# WELLD0_3Schematic.net
KiCad netlist of a schematic drawn in EAGLE
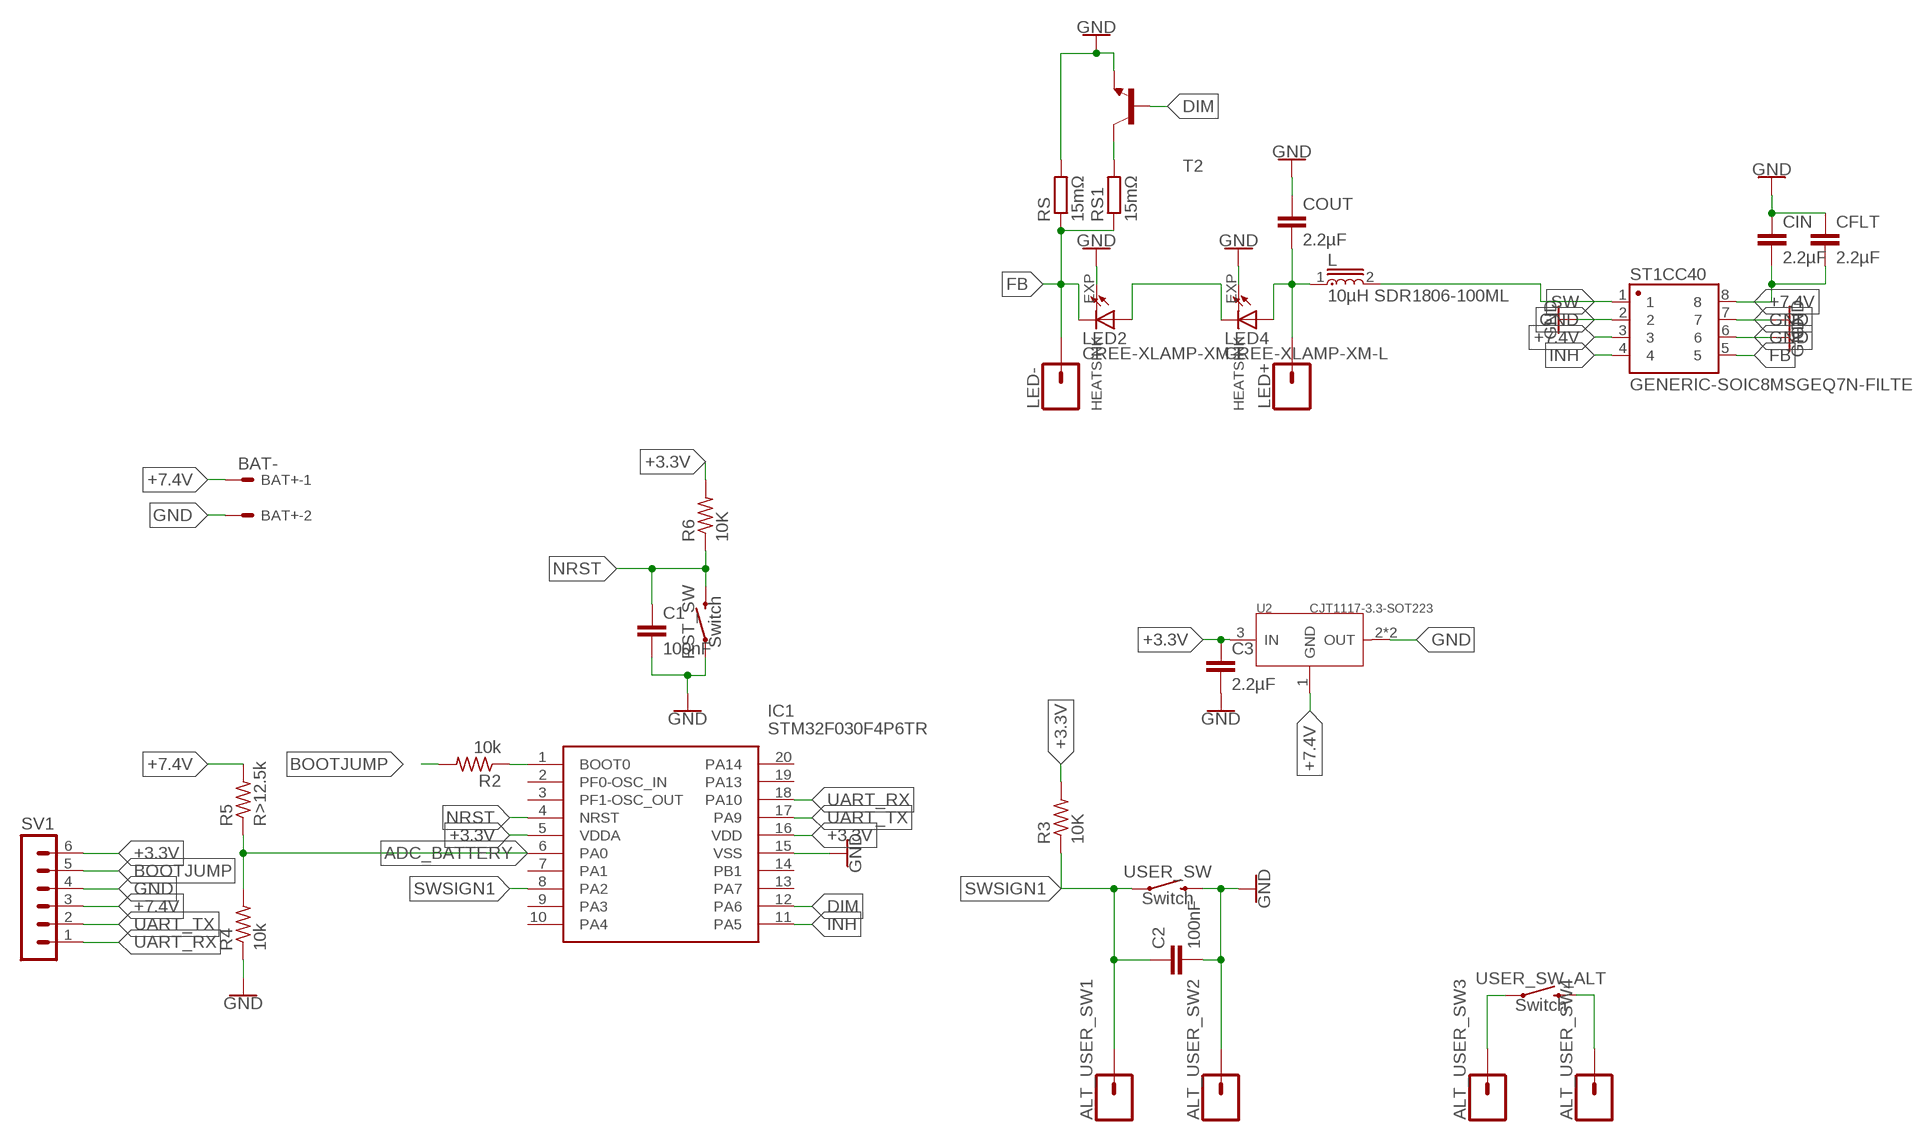
[diagram p0: schematic, sheet 1]

(export (version "E")
  (design (tool "Eeschema 10.0.6"))
  (components
    (comp (ref "ALT_USER_SW1")
      (value "CONN_01")
      (footprint "eagle-import:1X01")
      (libsource (lib "eagle-import") (part "CONN_01"))
    )
    (comp (ref "ALT_USER_SW2")
      (value "CONN_01")
      (footprint "eagle-import:1X01")
      (libsource (lib "eagle-import") (part "CONN_01"))
    )
    (comp (ref "ALT_USER_SW3")
      (value "CONN_01")
      (footprint "eagle-import:1X01")
      (libsource (lib "eagle-import") (part "CONN_01"))
    )
    (comp (ref "ALT_USER_SW4")
      (value "CONN_01")
      (footprint "eagle-import:1X01")
      (libsource (lib "eagle-import") (part "CONN_01"))
    )
    (comp (ref "BAT+")
      (value "BAT-")
      (footprint "eagle-import:6410-02")
      (fields (field (name "MF") "MOLEX"))
      (libsource (lib "eagle-import") (part "22-?-0227-2021"))
    )
    (comp (ref "C1")
      (value "100nF")
      (footprint "eagle-import:C0603")
      (libsource (lib "eagle-import") (part "C-EUC0603"))
    )
    (comp (ref "C2")
      (value "100nF")
      (footprint "eagle-import:C0603")
      (libsource (lib "eagle-import") (part "C-EUC0603"))
    )
    (comp (ref "C3")
      (value "2.2µF")
      (footprint "eagle-import:C0603")
      (libsource (lib "eagle-import") (part "C-EUC0603"))
    )
    (comp (ref "CFLT")
      (value "2.2µF")
      (footprint "eagle-import:C0603")
      (libsource (lib "eagle-import") (part "C-EUC0603"))
    )
    (comp (ref "CIN")
      (value "2.2µF")
      (footprint "eagle-import:C0603")
      (libsource (lib "eagle-import") (part "C-EUC0603"))
    )
    (comp (ref "COUT")
      (value "2.2µF")
      (footprint "eagle-import:C0603")
      (libsource (lib "eagle-import") (part "C-EUC0603"))
    )
    (comp (ref "IC1")
      (value "STM32F030F4P6TR")
      (footprint "eagle-import:SOP65P640X120-20N")
      (fields (field (name "RS_PART_NUMBER") "1688744"))
      (libsource (lib "eagle-import") (part "STM32F030F4P6TR"))
    )
    (comp (ref "L")
      (value "10µH SDR1806-100ML")
      (footprint "eagle-import:INDP1830X1400X690L250X260N")
      (fields
        (field (name "DIGI-KEY_PART_NUMBER") "SDR1806-470MLCT-ND")
        (field (name "MF") "Bourns")
        (field (name "MP") "SDR1806-470ML")
      )
      (libsource (lib "eagle-import") (part "SDR1806-470ML"))
    )
    (comp (ref "LED+")
      (value "CONN_01")
      (footprint "eagle-import:1X01")
      (libsource (lib "eagle-import") (part "CONN_01"))
    )
    (comp (ref "LED-")
      (value "CONN_01")
      (footprint "eagle-import:1X01")
      (libsource (lib "eagle-import") (part "CONN_01"))
    )
    (comp (ref "LED2")
      (value "CREE-XLAMP-XM-L")
      (footprint "eagle-import:CREE-XLAMP-XM-L")
      (libsource (lib "eagle-import") (part "CREE-XLAMP-XM-L"))
    )
    (comp (ref "LED4")
      (value "CREE-XLAMP-XM-L")
      (footprint "eagle-import:CREE-XLAMP-XM-L")
      (libsource (lib "eagle-import") (part "CREE-XLAMP-XM-L"))
    )
    (comp (ref "R2")
      (value "10k")
      (footprint "eagle-import:R0603")
      (libsource (lib "eagle-import") (part "R-US_R0603"))
    )
    (comp (ref "R3")
      (value "10K")
      (footprint "eagle-import:R0603")
      (libsource (lib "eagle-import") (part "R-US_R0603"))
    )
    (comp (ref "R4")
      (value "10k")
      (footprint "eagle-import:R0603")
      (libsource (lib "eagle-import") (part "R-US_R0603"))
    )
    (comp (ref "R5")
      (value "R>12.5k")
      (footprint "eagle-import:R0603")
      (libsource (lib "eagle-import") (part "R-US_R0603"))
    )
    (comp (ref "R6")
      (value "10K")
      (footprint "eagle-import:R0603")
      (libsource (lib "eagle-import") (part "R-US_R0603"))
    )
    (comp (ref "RS")
      (value "15mΩ")
      (footprint "eagle-import:M1206")
      (libsource (lib "eagle-import") (part "R-EU_M1206"))
    )
    (comp (ref "RS1")
      (value "15mΩ")
      (footprint "eagle-import:M1206")
      (libsource (lib "eagle-import") (part "R-EU_M1206"))
    )
    (comp (ref "RST_SW")
      (value "Switch")
      (footprint "eagle-import:TACTILE_SWITCH_SMD_6.2MM_TALL")
      (libsource (lib "eagle-import") (part "MOMENTARY-SWITCH-SPST-SMD-6.2MM-TALL"))
    )
    (comp (ref "ST1CC40")
      (value "GENERIC-SOIC8MSGEQ7N-FILTER")
      (footprint "eagle-import:SO08")
      (libsource (lib "eagle-import") (part "GENERIC-SOIC8MSGEQ7N-FILTER"))
    )
    (comp (ref "SV1")
      (value "MA06-1")
      (footprint "eagle-import:MA06-1")
      (libsource (lib "eagle-import") (part "MA06-1"))
    )
    (comp (ref "T2")
      (value "-NPN-SOT23-BEC")
      (footprint "eagle-import:SOT23-BEC")
      (libsource (lib "eagle-import") (part "-NPN-SOT23-BEC"))
    )
    (comp (ref "U2")
      (value "CJT1117-3.3-SOT223")
      (footprint "eagle-import:SOT-223")
      (fields (field (name "MPN") "CJT1117-3.3"))
      (libsource (lib "eagle-import") (part "PMIC-CJT1117-3.3(SOT223)"))
    )
    (comp (ref "USER_SW")
      (value "Switch")
      (footprint "eagle-import:TACTILE_SWITCH_SMD_6.2MM_TALL")
      (libsource (lib "eagle-import") (part "MOMENTARY-SWITCH-SPST-SMD-6.2MM-TALL"))
    )
    (comp (ref "USER_SW_ALT")
      (value "Switch")
      (footprint "eagle-import:TACTILE_SWITCH_SMD_6.2MM_TALL")
      (libsource (lib "eagle-import") (part "MOMENTARY-SWITCH-SPST-SMD-6.2MM-TALL"))
    )
  )
  (nets
    (net (code "1") (name "+3.3V") (class "Default")
      (node (ref "C3") (pin "1") (pinfunction "1_1") (pintype "passive"))
      (node (ref "IC1") (pin "16") (pinfunction "VDD_16") (pintype "power_in"))
      (node (ref "IC1") (pin "5") (pinfunction "VDDA_5") (pintype "power_in"))
      (node (ref "R3") (pin "2") (pinfunction "2_2") (pintype "passive"))
      (node (ref "R6") (pin "2") (pinfunction "2_2") (pintype "passive"))
      (node (ref "SV1") (pin "6") (pinfunction "6_6") (pintype "passive"))
      (node (ref "U2") (pin "3") (pinfunction "IN_3") (pintype "bidirectional"))
    )
    (net (code "2") (name "+7.4V") (class "Default")
      (node (ref "BAT+") (pin "1") (pinfunction "S_1") (pintype "passive"))
      (node (ref "CFLT") (pin "2") (pinfunction "2_2") (pintype "passive"))
      (node (ref "CIN") (pin "2") (pinfunction "2_2") (pintype "passive"))
      (node (ref "R5") (pin "2") (pinfunction "2_2") (pintype "passive"))
      (node (ref "ST1CC40") (pin "3") (pinfunction "3_3") (pintype "bidirectional"))
      (node (ref "ST1CC40") (pin "8") (pinfunction "8_8") (pintype "bidirectional"))
      (node (ref "SV1") (pin "3") (pinfunction "3_3") (pintype "passive"))
      (node (ref "U2") (pin "1") (pinfunction "GND_1") (pintype "bidirectional"))
    )
    (net (code "3") (name "ADC_BATTERY") (class "Default")
      (node (ref "IC1") (pin "6") (pinfunction "PA0_6") (pintype "bidirectional"))
      (node (ref "R4") (pin "2") (pinfunction "2_2") (pintype "passive"))
      (node (ref "R5") (pin "1") (pinfunction "1_1") (pintype "passive"))
    )
    (net (code "4") (name "BOOTJUMP") (class "Default")
      (node (ref "R2") (pin "2") (pinfunction "2_2") (pintype "passive"))
      (node (ref "SV1") (pin "5") (pinfunction "5_5") (pintype "passive"))
    )
    (net (code "5") (name "DIM") (class "Default")
      (node (ref "IC1") (pin "12") (pinfunction "PA6_12") (pintype "bidirectional"))
      (node (ref "T2") (pin "B") (pinfunction "B_B") (pintype "passive"))
    )
    (net (code "6") (name "FB") (class "Default")
      (node (ref "LED-") (pin "1") (pinfunction "1_1") (pintype "passive"))
      (node (ref "LED2") (pin "C") (pinfunction "C_C") (pintype "passive"))
      (node (ref "LED2") (pin "C@1") (pinfunction "C_C@1") (pintype "passive"))
      (node (ref "RS") (pin "1") (pinfunction "1_1") (pintype "passive"))
      (node (ref "RS1") (pin "1") (pinfunction "1_1") (pintype "passive"))
      (node (ref "ST1CC40") (pin "5") (pinfunction "5_5") (pintype "bidirectional"))
    )
    (net (code "7") (name "GND") (class "Default")
      (node (ref "ALT_USER_SW2") (pin "1") (pinfunction "1_1") (pintype "passive"))
      (node (ref "BAT+") (pin "2") (pinfunction "S_2") (pintype "passive"))
      (node (ref "C1") (pin "2") (pinfunction "2_2") (pintype "passive"))
      (node (ref "C2") (pin "2") (pinfunction "2_2") (pintype "passive"))
      (node (ref "C3") (pin "2") (pinfunction "2_2") (pintype "passive"))
      (node (ref "CFLT") (pin "1") (pinfunction "1_1") (pintype "passive"))
      (node (ref "CIN") (pin "1") (pinfunction "1_1") (pintype "passive"))
      (node (ref "COUT") (pin "1") (pinfunction "1_1") (pintype "passive"))
      (node (ref "IC1") (pin "15") (pinfunction "VSS_15") (pintype "power_in"))
      (node (ref "LED2") (pin "EXP") (pinfunction "HEATSINK_EXP") (pintype "bidirectional"))
      (node (ref "LED4") (pin "EXP") (pinfunction "HEATSINK_EXP") (pintype "bidirectional"))
      (node (ref "R4") (pin "1") (pinfunction "1_1") (pintype "passive"))
      (node (ref "RS") (pin "2") (pinfunction "2_2") (pintype "passive"))
      (node (ref "RST_SW") (pin "A2") (pinfunction "1_A2") (pintype "passive"))
      (node (ref "ST1CC40") (pin "2") (pinfunction "2_2") (pintype "bidirectional"))
      (node (ref "ST1CC40") (pin "6") (pinfunction "6_6") (pintype "bidirectional"))
      (node (ref "ST1CC40") (pin "7") (pinfunction "7_7") (pintype "bidirectional"))
      (node (ref "SV1") (pin "4") (pinfunction "4_4") (pintype "passive"))
      (node (ref "T2") (pin "E") (pinfunction "E_E") (pintype "passive"))
      (node (ref "U2") (pin "2") (pinfunction "OUT_2") (pintype "bidirectional"))
      (node (ref "U2") (pin "TER") (pinfunction "OUT_TER") (pintype "bidirectional"))
      (node (ref "USER_SW") (pin "B2") (pinfunction "2_B2") (pintype "passive"))
    )
    (net (code "8") (name "INH") (class "Default")
      (node (ref "IC1") (pin "11") (pinfunction "PA5_11") (pintype "bidirectional"))
      (node (ref "ST1CC40") (pin "4") (pinfunction "4_4") (pintype "bidirectional"))
    )
    (net (code "9") (name "NRST") (class "Default")
      (node (ref "C1") (pin "1") (pinfunction "1_1") (pintype "passive"))
      (node (ref "IC1") (pin "4") (pinfunction "NRST_4") (pintype "input"))
      (node (ref "R6") (pin "1") (pinfunction "1_1") (pintype "passive"))
      (node (ref "RST_SW") (pin "B2") (pinfunction "2_B2") (pintype "passive"))
    )
    (net (code "10") (name "Net-(COUT-Pad2)") (class "Default")
      (node (ref "COUT") (pin "2") (pinfunction "2_2") (pintype "passive"))
      (node (ref "L") (pin "1") (pinfunction "1_1") (pintype "passive"))
      (node (ref "LED+") (pin "1") (pinfunction "1_1") (pintype "passive"))
      (node (ref "LED4") (pin "A") (pinfunction "A_A") (pintype "passive"))
      (node (ref "LED4") (pin "A@1") (pinfunction "A_A@1") (pintype "passive"))
    )
    (net (code "11") (name "Net-(IC1-BOOT0)") (class "Default")
      (node (ref "IC1") (pin "1") (pinfunction "BOOT0_1") (pintype "bidirectional"))
      (node (ref "R2") (pin "1") (pinfunction "1_1") (pintype "passive"))
    )
    (net (code "12") (name "Net-(LED2-A-PadA@1)") (class "Default")
      (node (ref "LED2") (pin "A") (pinfunction "A_A") (pintype "passive"))
      (node (ref "LED2") (pin "A@1") (pinfunction "A_A@1") (pintype "passive"))
      (node (ref "LED4") (pin "C") (pinfunction "C_C") (pintype "passive"))
      (node (ref "LED4") (pin "C@1") (pinfunction "C_C@1") (pintype "passive"))
    )
    (net (code "13") (name "Net-(RS1-Pad2)") (class "Default")
      (node (ref "RS1") (pin "2") (pinfunction "2_2") (pintype "passive"))
      (node (ref "T2") (pin "C") (pinfunction "C_C") (pintype "passive"))
    )
    (net (code "14") (name "Net-(USER_SW_ALT-1)") (class "Default")
      (node (ref "ALT_USER_SW3") (pin "1") (pinfunction "1_1") (pintype "passive"))
      (node (ref "USER_SW_ALT") (pin "A2") (pinfunction "1_A2") (pintype "passive"))
    )
    (net (code "15") (name "Net-(USER_SW_ALT-2)") (class "Default")
      (node (ref "ALT_USER_SW4") (pin "1") (pinfunction "1_1") (pintype "passive"))
      (node (ref "USER_SW_ALT") (pin "B2") (pinfunction "2_B2") (pintype "passive"))
    )
    (net (code "16") (name "SW") (class "Default")
      (node (ref "L") (pin "2") (pinfunction "2_2") (pintype "passive"))
      (node (ref "ST1CC40") (pin "1") (pinfunction "1_1") (pintype "bidirectional"))
    )
    (net (code "17") (name "SWSIGN1") (class "Default")
      (node (ref "ALT_USER_SW1") (pin "1") (pinfunction "1_1") (pintype "passive"))
      (node (ref "C2") (pin "1") (pinfunction "1_1") (pintype "passive"))
      (node (ref "IC1") (pin "8") (pinfunction "PA2_8") (pintype "bidirectional"))
      (node (ref "R3") (pin "1") (pinfunction "1_1") (pintype "passive"))
      (node (ref "USER_SW") (pin "A2") (pinfunction "1_A2") (pintype "passive"))
    )
    (net (code "18") (name "UART_RX") (class "Default")
      (node (ref "IC1") (pin "18") (pinfunction "PA10_18") (pintype "bidirectional"))
      (node (ref "SV1") (pin "1") (pinfunction "1_1") (pintype "passive"))
    )
    (net (code "19") (name "UART_TX") (class "Default")
      (node (ref "IC1") (pin "17") (pinfunction "PA9_17") (pintype "bidirectional"))
      (node (ref "SV1") (pin "2") (pinfunction "2_2") (pintype "passive"))
    )
    (net (code "20") (name "unconnected-(IC1-PA1-Pad7)") (class "Default")
      (node (ref "IC1") (pin "7") (pinfunction "PA1_7") (pintype "bidirectional"))
    )
    (net (code "21") (name "unconnected-(IC1-PA3-Pad9)") (class "Default")
      (node (ref "IC1") (pin "9") (pinfunction "PA3_9") (pintype "bidirectional"))
    )
    (net (code "22") (name "unconnected-(IC1-PA4-Pad10)") (class "Default")
      (node (ref "IC1") (pin "10") (pinfunction "PA4_10") (pintype "bidirectional"))
    )
    (net (code "23") (name "unconnected-(IC1-PA7-Pad13)") (class "Default")
      (node (ref "IC1") (pin "13") (pinfunction "PA7_13") (pintype "bidirectional"))
    )
    (net (code "24") (name "unconnected-(IC1-PA13-Pad19)") (class "Default")
      (node (ref "IC1") (pin "19") (pinfunction "PA13_19") (pintype "bidirectional"))
    )
    (net (code "25") (name "unconnected-(IC1-PA14-Pad20)") (class "Default")
      (node (ref "IC1") (pin "20") (pinfunction "PA14_20") (pintype "bidirectional"))
    )
    (net (code "26") (name "unconnected-(IC1-PB1-Pad14)") (class "Default")
      (node (ref "IC1") (pin "14") (pinfunction "PB1_14") (pintype "bidirectional"))
    )
    (net (code "27") (name "unconnected-(IC1-PF0-OSC_IN-Pad2)") (class "Default")
      (node (ref "IC1") (pin "2") (pinfunction "PF0-OSC_IN_2") (pintype "input"))
    )
    (net (code "28") (name "unconnected-(IC1-PF1-OSC_OUT-Pad3)") (class "Default")
      (node (ref "IC1") (pin "3") (pinfunction "PF1-OSC_OUT_3") (pintype "output"))
    )
  )
)
